# Sheet2.net
KiCad netlist of a schematic drawn in Altium Designer
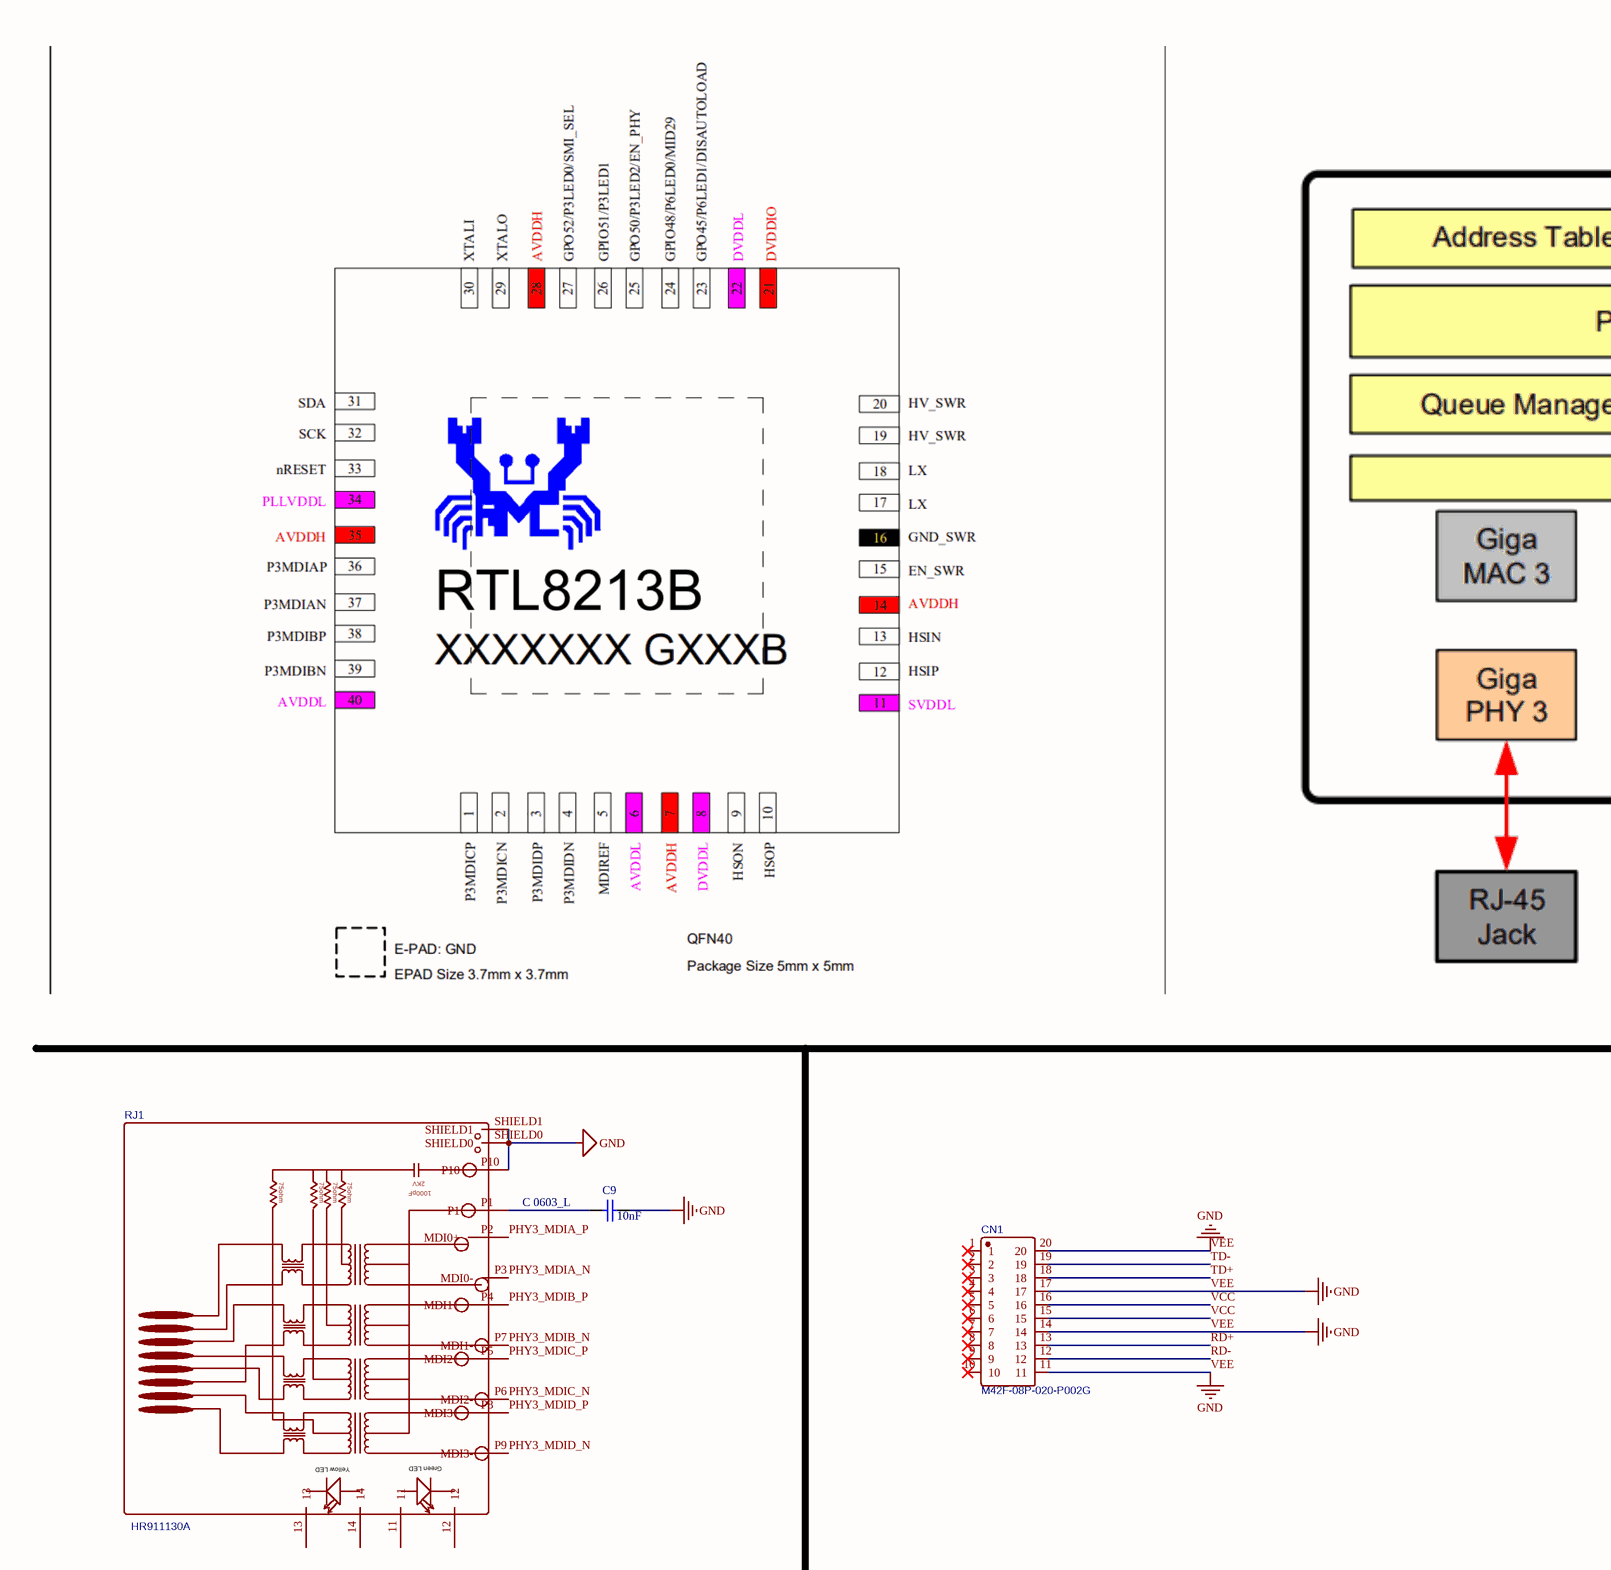
[diagram p0: Sheet2.SchDoc, top left]
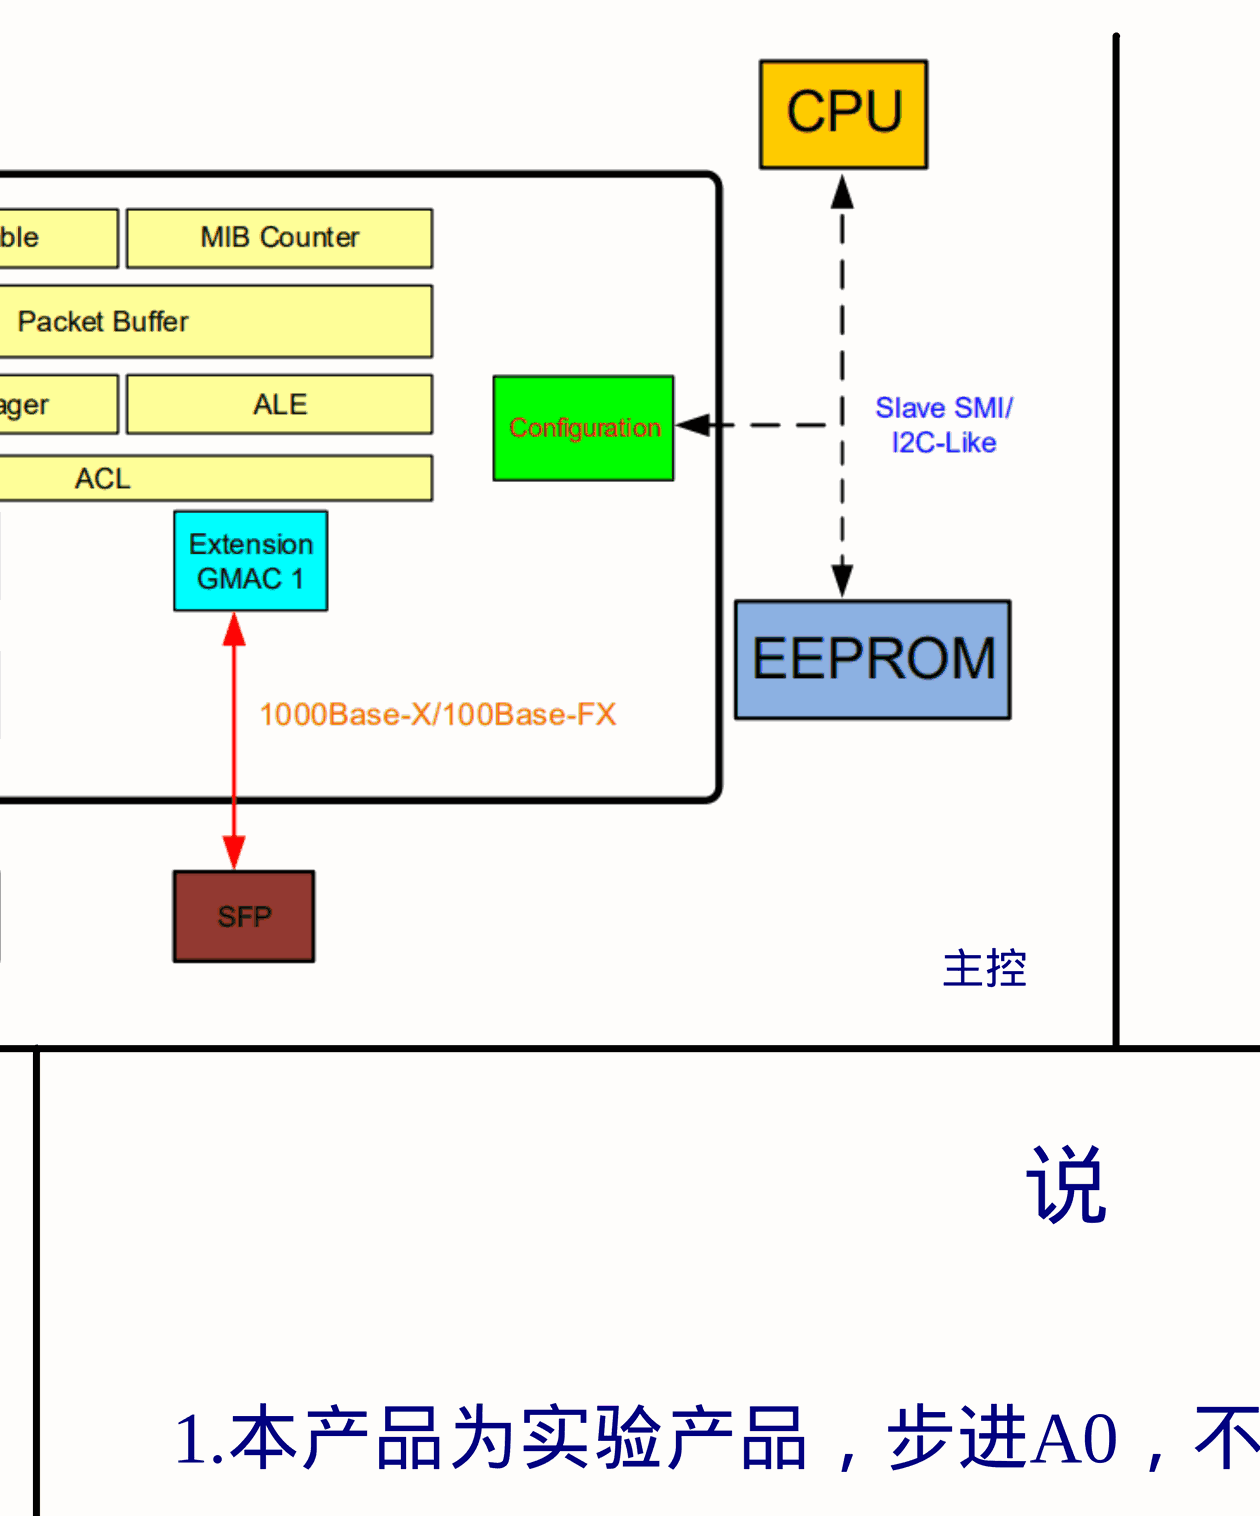
[diagram p1: Sheet2.SchDoc, top middle]
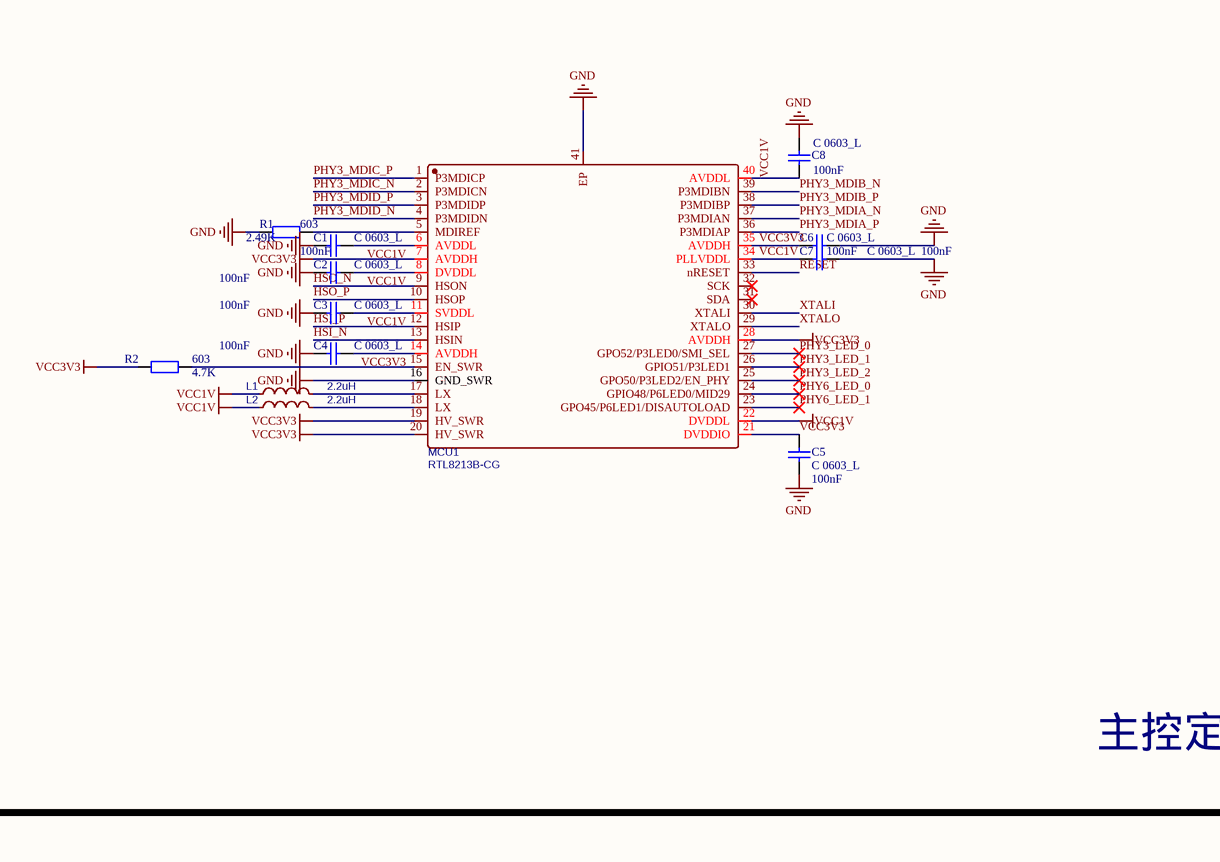
[diagram p2: Sheet2.SchDoc, top right]
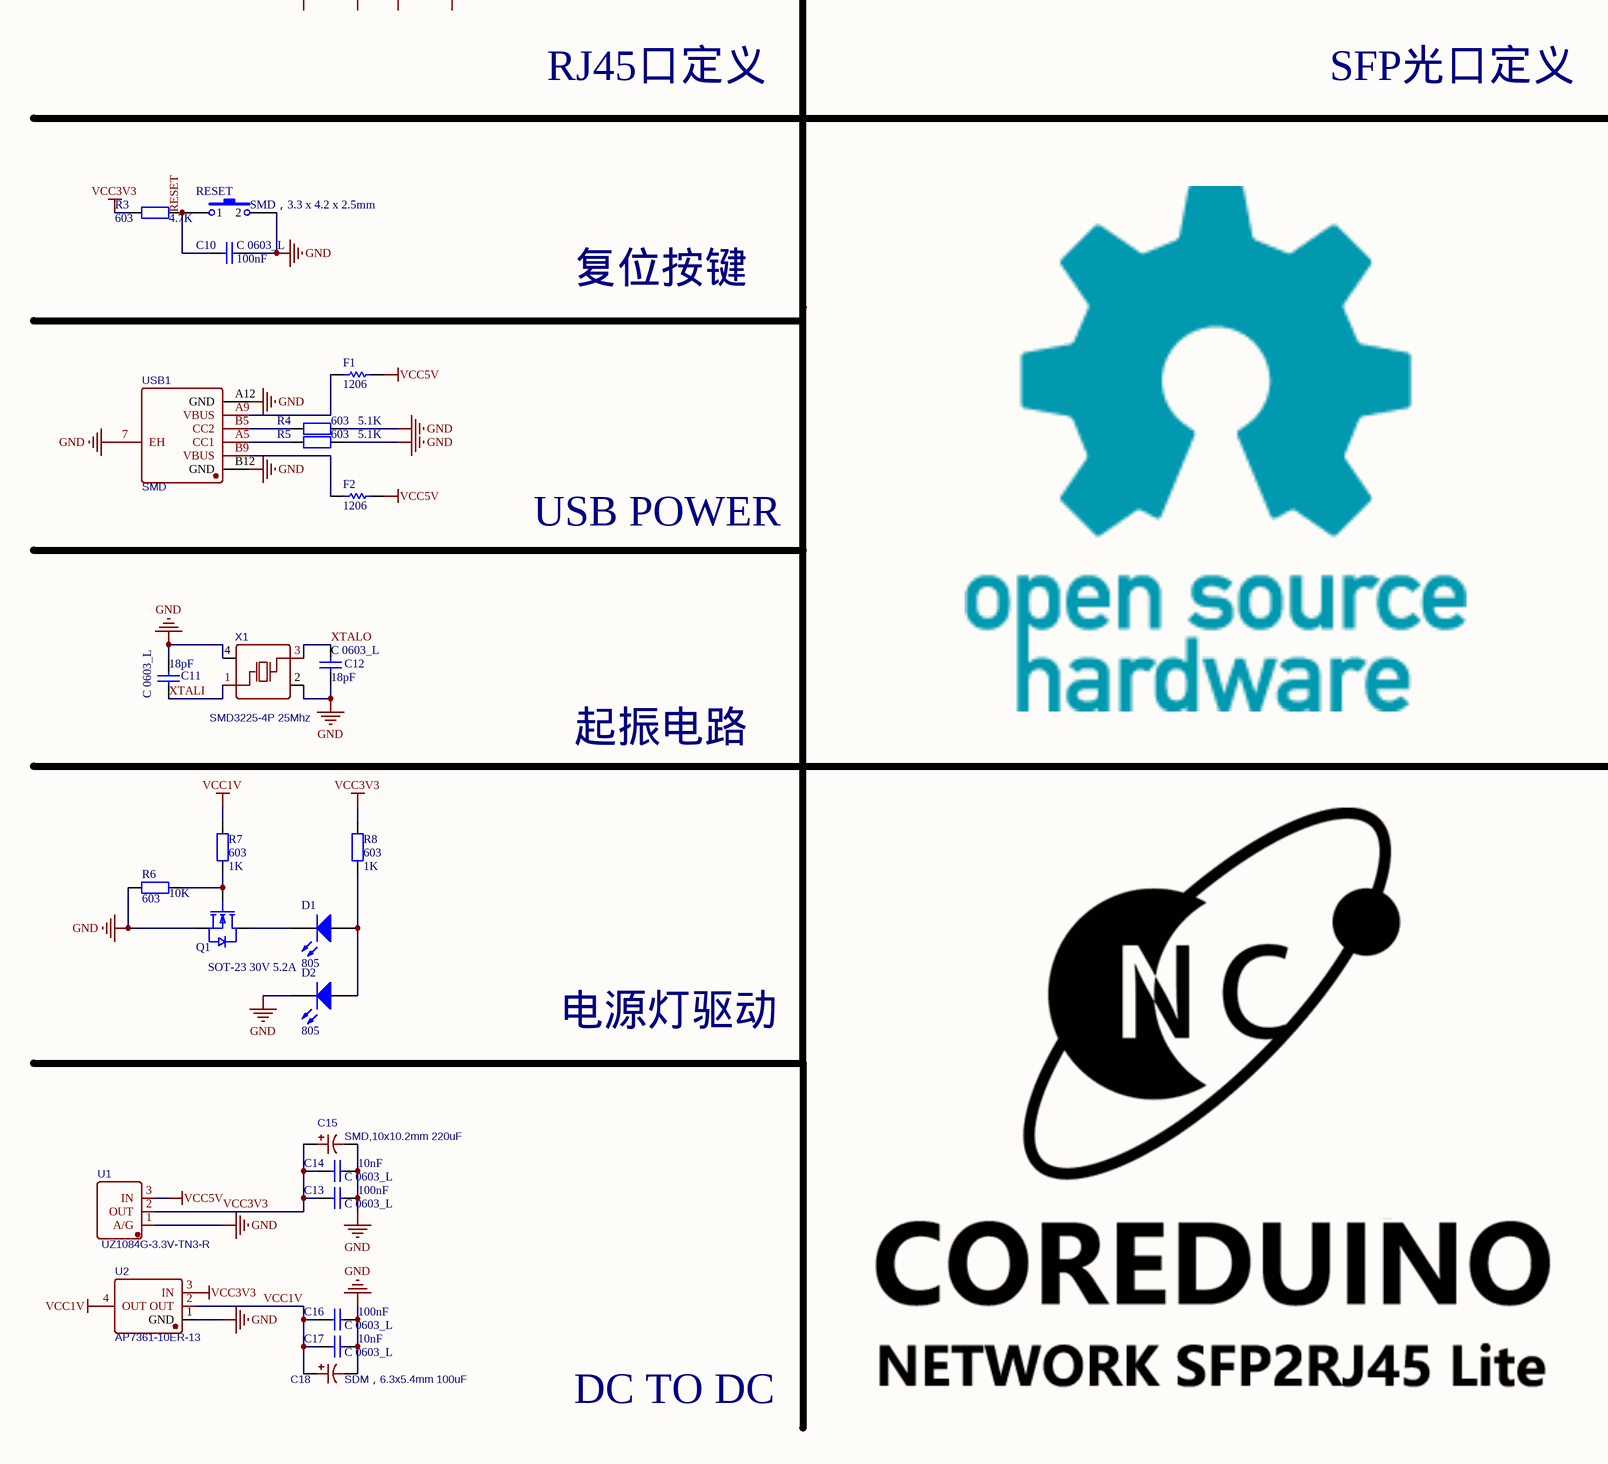
[diagram p3: Sheet2.SchDoc, bottom left]
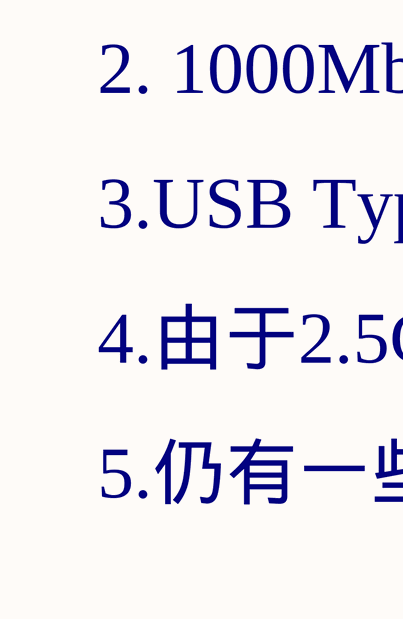
[diagram p4: Sheet2.SchDoc, bottom middle]

(export (version "E")
  (design (tool "Eeschema 10.0.6"))
  (components
    (comp (ref "C1")
      (value "C 0603_L")
      (footprint "C 0603_L")
      (description "贴片电容器（Capacitor）")
      (fields (field (name "ALTIUM_VALUE") "100nF") (field (name "PUBLISHER") "Altium Limited"))
      (libsource (lib "BaseLib") (part "C 0603_L"))
    )
    (comp (ref "C2")
      (value "C 0603_L")
      (footprint "C 0603_L")
      (description "贴片电容器（Capacitor）")
      (fields (field (name "ALTIUM_VALUE") "100nF") (field (name "PUBLISHER") "Altium Limited"))
      (libsource (lib "BaseLib") (part "C 0603_L"))
    )
    (comp (ref "C3")
      (value "C 0603_L")
      (footprint "C 0603_L")
      (description "贴片电容器（Capacitor）")
      (fields (field (name "ALTIUM_VALUE") "100nF") (field (name "PUBLISHER") "Altium Limited"))
      (libsource (lib "BaseLib") (part "C 0603_L"))
    )
    (comp (ref "C4")
      (value "C 0603_L")
      (footprint "C 0603_L")
      (description "贴片电容器（Capacitor）")
      (fields (field (name "ALTIUM_VALUE") "100nF") (field (name "PUBLISHER") "Altium Limited"))
      (libsource (lib "BaseLib") (part "C 0603_L"))
    )
    (comp (ref "C5")
      (value "C 0603_L")
      (footprint "C 0603_L")
      (description "贴片电容器（Capacitor）")
      (fields (field (name "ALTIUM_VALUE") "100nF") (field (name "PUBLISHER") "Altium Limited"))
      (libsource (lib "BaseLib") (part "C 0603_L"))
    )
    (comp (ref "C6")
      (value "C 0603_L")
      (footprint "C 0603_L")
      (description "贴片电容器（Capacitor）")
      (fields (field (name "ALTIUM_VALUE") "100nF") (field (name "PUBLISHER") "Altium Limited"))
      (libsource (lib "BaseLib") (part "C 0603_L"))
    )
    (comp (ref "C7")
      (value "C 0603_L")
      (footprint "C 0603_L")
      (description "贴片电容器（Capacitor）")
      (fields (field (name "ALTIUM_VALUE") "100nF") (field (name "PUBLISHER") "Altium Limited"))
      (libsource (lib "BaseLib") (part "C 0603_L"))
    )
    (comp (ref "C8")
      (value "C 0603_L")
      (footprint "C 0603_L")
      (description "贴片电容器（Capacitor）")
      (fields (field (name "ALTIUM_VALUE") "100nF") (field (name "PUBLISHER") "Altium Limited"))
      (libsource (lib "BaseLib") (part "C 0603_L"))
    )
    (comp (ref "C9")
      (value "C 0603_L")
      (footprint "C 0603_L")
      (description "贴片电容器（Capacitor）")
      (fields (field (name "ALTIUM_VALUE") "10nF") (field (name "PUBLISHER") "Altium Limited"))
      (libsource (lib "BaseLib") (part "C 0603_L"))
    )
    (comp (ref "C10")
      (value "C 0603_L")
      (footprint "C 0603_L")
      (description "贴片电容器（Capacitor）")
      (fields (field (name "ALTIUM_VALUE") "100nF") (field (name "PUBLISHER") "Altium Limited"))
      (libsource (lib "BaseLib") (part "C 0603_L"))
    )
    (comp (ref "C11")
      (value "C 0603_L")
      (footprint "C 0603_L")
      (description "贴片电容器（Capacitor）")
      (fields (field (name "ALTIUM_VALUE") "18pF") (field (name "PUBLISHER") "Altium Limited"))
      (libsource (lib "BaseLib") (part "C 0603_L"))
    )
    (comp (ref "C12")
      (value "C 0603_L")
      (footprint "C 0603_L")
      (description "贴片电容器（Capacitor）")
      (fields (field (name "ALTIUM_VALUE") "18pF") (field (name "PUBLISHER") "Altium Limited"))
      (libsource (lib "BaseLib") (part "C 0603_L"))
    )
    (comp (ref "C13")
      (value "C 0603_L")
      (footprint "C 0603_L")
      (description "贴片电容器（Capacitor）")
      (fields (field (name "ALTIUM_VALUE") "100nF") (field (name "PUBLISHER") "Altium Limited"))
      (libsource (lib "BaseLib") (part "C 0603_L"))
    )
    (comp (ref "C14")
      (value "C 0603_L")
      (footprint "C 0603_L")
      (description "贴片电容器（Capacitor）")
      (fields (field (name "ALTIUM_VALUE") "10nF") (field (name "PUBLISHER") "Altium Limited"))
      (libsource (lib "BaseLib") (part "C 0603_L"))
    )
    (comp (ref "C15")
      (value "SMD,10x10.2mm 220uF")
      (footprint "CAP-SMD_BD10.0-L10.3-W10.3-LS11.0-FD")
      (description "贴片铝电解电容器（Capacitor）")
      (fields
        (field (name "BOM_SUPPLIER PART") "C2887271")
        (field (name "BOM_MANUFACTURER PART") "RVT220UF50V67RV0021")
        (field (name "CONTRIBUTOR") "LCSC")
      )
      (libsource (lib "BaseLib") (part "RVT220UF50V67RV0021"))
    )
    (comp (ref "C16")
      (value "C 0603_L")
      (footprint "C 0603_L")
      (description "贴片电容器（Capacitor）")
      (fields (field (name "ALTIUM_VALUE") "100nF") (field (name "PUBLISHER") "Altium Limited"))
      (libsource (lib "BaseLib") (part "C 0603_L"))
    )
    (comp (ref "C17")
      (value "C 0603_L")
      (footprint "C 0603_L")
      (description "贴片电容器（Capacitor）")
      (fields (field (name "ALTIUM_VALUE") "10nF") (field (name "PUBLISHER") "Altium Limited"))
      (libsource (lib "BaseLib") (part "C 0603_L"))
    )
    (comp (ref "C18")
      (value "SDM，6.3x5.4mm 100uF")
      (footprint "CAP-SMD_BD6.3-L6.6-W6.6-LS7.2-FD")
      (description "贴片铝电解电容器（Capacitor）")
      (fields
        (field (name "BOM_SUPPLIER PART") "C2887276")
        (field (name "BOM_MANUFACTURER PART") "RVT100UF16V67RV0016")
        (field (name "CONTRIBUTOR") "LCSC")
      )
      (libsource (lib "BaseLib") (part "RVT100UF16V67RV0016"))
    )
    (comp (ref "CN1")
      (value "M42F-08P-020-P002G")
      (footprint "CONN-SMD_20P-P0.80-H_M42F-08P-020-P002G")
      (description "SFP+万兆光模块口（SFP+ Jack）")
      (fields (field (name "BOM_SUPPLIER PART") "C404107") (field (name "CONTRIBUTOR") "LCSC"))
      (libsource (lib "BaseLib") (part "M42F-08P-020-P002G"))
    )
    (comp (ref "D1")
      (value "805")
      (footprint "LED 0805G")
      (description "贴片发光二极管（LED）")
      (fields (field (name "PUBLISHER") "Altium Limited"))
      (libsource (lib "BaseLib") (part "LED 0805G 绿"))
    )
    (comp (ref "D2")
      (value "805")
      (footprint "LED 0805G")
      (description "贴片发光二极管（LED）")
      (fields (field (name "PUBLISHER") "Altium Limited"))
      (libsource (lib "BaseLib") (part "LED 0805G 绿"))
    )
    (comp (ref "F1")
      (value "1206")
      (footprint "FU 1206")
      (description "自恢复保险丝（Fuse）")
      (fields (field (name "PUBLISHER") "Altium Limited"))
      (libsource (lib "BaseLib") (part "nsmd150"))
    )
    (comp (ref "F2")
      (value "1206")
      (footprint "FU 1206")
      (description "自恢复保险丝（Fuse）")
      (fields (field (name "PUBLISHER") "Altium Limited"))
      (libsource (lib "BaseLib") (part "nsmd150"))
    )
    (comp (ref "L1")
      (value "2.2uH")
      (footprint "L0603")
      (description "贴片电感（Inductors）")
      (fields
        (field (name "BOM_MANUFACTURER PART") "SDFL1608Q2R2KTF")
        (field (name "BOM_SUPPLIER PART") "C1033")
      )
      (libsource (lib "BaseLib") (part "SDFL1608Q2R2KTF"))
    )
    (comp (ref "L2")
      (value "2.2uH")
      (footprint "L0603")
      (description "贴片电感（Inductors）")
      (fields
        (field (name "BOM_MANUFACTURER PART") "SDFL1608Q2R2KTF")
        (field (name "BOM_SUPPLIER PART") "C1033")
      )
      (libsource (lib "BaseLib") (part "SDFL1608Q2R2KTF"))
    )
    (comp (ref "MCU1")
      (value "RTL8213B-CG")
      (footprint "QFN-40_L5.0-W5.0-P0.40-BL-EP3.7")
      (description "以太网转换芯片（Network）")
      (fields (field (name "BOM_SUPPLIER PART") "C2766076") (field (name "CONTRIBUTOR") "LCSC"))
      (libsource (lib "BaseLib") (part "RTL8213B-CG"))
    )
    (comp (ref "Q1")
      (value "SOT-23 30V 5.2A")
      (footprint "AO3400A")
      (description "场效应管（MOSFET）")
      (fields (field (name "MANUFACTURER") "Nexperia(安世)") (field (name "MANUFACTURER PART") "2N7002,215"))
      (libsource (lib "BaseLib") (part "AO3400A"))
    )
    (comp (ref "R1")
      (value "603")
      (footprint "R 0603_L")
      (description "贴片电阻（Resistor）")
      (fields (field (name "ALTIUM_VALUE") "2.49K") (field (name "PUBLISHER") "Altium Limited"))
      (libsource (lib "BaseLib") (part "R 0603_L"))
    )
    (comp (ref "R2")
      (value "603")
      (footprint "R 0603_L")
      (description "贴片电阻（Resistor）")
      (fields (field (name "ALTIUM_VALUE") "4.7K") (field (name "PUBLISHER") "Altium Limited"))
      (libsource (lib "BaseLib") (part "R 0603_L"))
    )
    (comp (ref "R3")
      (value "603")
      (footprint "R 0603_L")
      (description "贴片电阻（Resistor）")
      (fields (field (name "ALTIUM_VALUE") "4.7K") (field (name "PUBLISHER") "Altium Limited"))
      (libsource (lib "BaseLib") (part "R 0603_L"))
    )
    (comp (ref "R4")
      (value "603")
      (footprint "R 0603_L")
      (description "贴片电阻（Resistor）")
      (fields (field (name "ALTIUM_VALUE") "5.1K") (field (name "PUBLISHER") "Altium Limited"))
      (libsource (lib "BaseLib") (part "R 0603_L"))
    )
    (comp (ref "R5")
      (value "603")
      (footprint "R 0603_L")
      (description "贴片电阻（Resistor）")
      (fields (field (name "ALTIUM_VALUE") "5.1K") (field (name "PUBLISHER") "Altium Limited"))
      (libsource (lib "BaseLib") (part "R 0603_L"))
    )
    (comp (ref "R6")
      (value "603")
      (footprint "R 0603_L")
      (description "贴片电阻（Resistor）")
      (fields (field (name "ALTIUM_VALUE") "10K") (field (name "PUBLISHER") "Altium Limited"))
      (libsource (lib "BaseLib") (part "R 0603_L"))
    )
    (comp (ref "R7")
      (value "603")
      (footprint "R 0603_L")
      (description "贴片电阻（Resistor）")
      (fields (field (name "ALTIUM_VALUE") "1K") (field (name "PUBLISHER") "Altium Limited"))
      (libsource (lib "") (part "R 0603_L_1"))
    )
    (comp (ref "R8")
      (value "603")
      (footprint "R 0603_L")
      (description "贴片电阻（Resistor）")
      (fields (field (name "ALTIUM_VALUE") "1K") (field (name "PUBLISHER") "Altium Limited"))
      (libsource (lib "") (part "R 0603_L_1"))
    )
    (comp (ref "RESET")
      (value "SMD，3.3 x 4.2 x 2.5mm")
      (footprint "SMD-3.2*4.2")
      (description "轻触开关（Touch Switch）")
      (fields (field (name "PUBLISHER") "Altium Limited"))
      (libsource (lib "BaseLib") (part "260GF"))
    )
    (comp (ref "RJ1")
      (value "HR911130A")
      (footprint "RJ45-TH_HR911130A")
      (description "单插带灯以太网接口（RJ45）")
      (fields (field (name "BOM_SUPPLIER PART") "C54408"))
      (libsource (lib "BaseLib") (part "HR911130A"))
    )
    (comp (ref "U1")
      (value "UZ1084G-3.3V-TN3-R")
      (footprint "TO-252-3_L6.5-W5.8-P4.58-TL")
      (description "线性稳压器（LDO）")
      (fields (field (name "BOM_SUPPLIER PART") "C84897"))
      (libsource (lib "BaseLib") (part "UZ1084G-3.3V-TN3-R"))
    )
    (comp (ref "U2")
      (value "AP7361-10ER-13")
      (footprint "SOT-223_L6.5-W3.5-P2.30-LS7.0-BR")
      (description "线性稳压器（LDO）")
      (fields (field (name "BOM_SUPPLIER PART") "C460389") (field (name "CONTRIBUTOR") "LCSC"))
      (libsource (lib "BaseLib") (part "AP7361-10ER-13"))
    )
    (comp (ref "USB1")
      (value "SMD")
      (footprint "TYPE-C-SMD_TYPE-C-6P")
      (description "通用通信总线接口（USB）")
      (fields
        (field (name "BOM_SUPPLIER PART") "C456012")
        (field (name "BOM_MANUFACTURER PART") "TYPE-C 6P")
        (field (name "CONTRIBUTOR") "LCSC")
      )
      (libsource (lib "BaseLib") (part "TYPE-C 6P QT"))
    )
    (comp (ref "X1")
      (value "SMD3225-4P 25Mhz")
      (footprint "OSC-SMD_4P-L3.2-W2.5-BL")
      (description "无源晶振（Crystal）")
      (fields
        (field (name "BOM_SUPPLIER PART") "C117869")
        (field (name "BOM_MANUFACTURER PART") "XXCEELNANF-25MHZ")
        (field (name "CONTRIBUTOR") "LCSC")
      )
      (libsource (lib "BaseLib") (part "XXCEELNANF-25MHZ"))
    )
  )
  (nets
    (net (code "1") (name "/HSI_N") (class "Default")
      (node (ref "MCU1") (pin "13") (pinfunction "HSIN_13") (pintype "passive"))
    )
    (net (code "2") (name "/HSI_P") (class "Default")
      (node (ref "MCU1") (pin "12") (pinfunction "HSIP_12") (pintype "passive"))
    )
    (net (code "3") (name "/HSO_N") (class "Default")
      (node (ref "MCU1") (pin "9") (pinfunction "HSON_9") (pintype "passive"))
    )
    (net (code "4") (name "/HSO_P") (class "Default")
      (node (ref "MCU1") (pin "10") (pinfunction "HSOP_10") (pintype "passive"))
    )
    (net (code "5") (name "/PHY3_LED_0") (class "Default")
      (node (ref "MCU1") (pin "27") (pinfunction "GPO52/P3LED0/SMI_SEL_27") (pintype "passive+no_connect"))
    )
    (net (code "6") (name "/PHY3_LED_1") (class "Default")
      (node (ref "MCU1") (pin "26") (pinfunction "GPIO51/P3LED1_26") (pintype "passive+no_connect"))
    )
    (net (code "7") (name "/PHY3_LED_2") (class "Default")
      (node (ref "MCU1") (pin "25") (pinfunction "GPO50/P3LED2/EN_PHY_25") (pintype "passive+no_connect"))
    )
    (net (code "8") (name "/PHY3_MDIA_N") (class "Default")
      (node (ref "MCU1") (pin "37") (pinfunction "P3MDIAN_37") (pintype "passive"))
      (node (ref "RJ1") (pin "P3") (pinfunction "MDI0-_P3") (pintype "passive"))
    )
    (net (code "9") (name "/PHY3_MDIA_P") (class "Default")
      (node (ref "MCU1") (pin "36") (pinfunction "P3MDIAP_36") (pintype "passive"))
      (node (ref "RJ1") (pin "P2") (pinfunction "MDI0+_P2") (pintype "passive"))
    )
    (net (code "10") (name "/PHY3_MDIB_N") (class "Default")
      (node (ref "MCU1") (pin "39") (pinfunction "P3MDIBN_39") (pintype "passive"))
      (node (ref "RJ1") (pin "P7") (pinfunction "MDI1-_P7") (pintype "passive"))
    )
    (net (code "11") (name "/PHY3_MDIB_P") (class "Default")
      (node (ref "MCU1") (pin "38") (pinfunction "P3MDIBP_38") (pintype "passive"))
      (node (ref "RJ1") (pin "P4") (pinfunction "MDI1+_P4") (pintype "passive"))
    )
    (net (code "12") (name "/PHY3_MDIC_N") (class "Default")
      (node (ref "MCU1") (pin "2") (pinfunction "P3MDICN_2") (pintype "passive"))
      (node (ref "RJ1") (pin "P6") (pinfunction "MDI2-_P6") (pintype "passive"))
    )
    (net (code "13") (name "/PHY3_MDIC_P") (class "Default")
      (node (ref "MCU1") (pin "1") (pinfunction "P3MDICP_1") (pintype "passive"))
      (node (ref "RJ1") (pin "P5") (pinfunction "MDI2+_P5") (pintype "passive"))
    )
    (net (code "14") (name "/PHY3_MDID_N") (class "Default")
      (node (ref "MCU1") (pin "4") (pinfunction "P3MDIDN_4") (pintype "passive"))
      (node (ref "RJ1") (pin "P9") (pinfunction "MDI3-_P9") (pintype "passive"))
    )
    (net (code "15") (name "/PHY3_MDID_P") (class "Default")
      (node (ref "MCU1") (pin "3") (pinfunction "P3MDIDP_3") (pintype "passive"))
      (node (ref "RJ1") (pin "P8") (pinfunction "MDI3+_P8") (pintype "passive"))
    )
    (net (code "16") (name "/PHY6_LED_0") (class "Default")
      (node (ref "MCU1") (pin "24") (pinfunction "GPIO48/P6LED0/MID29_24") (pintype "passive+no_connect"))
    )
    (net (code "17") (name "/PHY6_LED_1") (class "Default")
      (node (ref "MCU1") (pin "23") (pinfunction "GPO45/P6LED1/DISAUTOLOAD_23") (pintype "passive+no_connect"))
    )
    (net (code "18") (name "/RD+") (class "Default")
      (node (ref "CN1") (pin "13") (pinfunction "13_13") (pintype "passive"))
    )
    (net (code "19") (name "/RD-") (class "Default")
      (node (ref "CN1") (pin "12") (pinfunction "12_12") (pintype "passive"))
    )
    (net (code "20") (name "/RESET") (class "Default")
      (node (ref "C10") (pin "1") (pinfunction "1_1") (pintype "passive"))
      (node (ref "MCU1") (pin "33") (pinfunction "nRESET_33") (pintype "passive"))
      (node (ref "R3") (pin "2") (pinfunction "2_2") (pintype "passive"))
      (node (ref "RESET") (pin "1") (pinfunction "1_1") (pintype "passive"))
    )
    (net (code "21") (name "/TD+") (class "Default")
      (node (ref "CN1") (pin "18") (pinfunction "18_18") (pintype "passive"))
    )
    (net (code "22") (name "/TD-") (class "Default")
      (node (ref "CN1") (pin "19") (pinfunction "19_19") (pintype "passive"))
    )
    (net (code "23") (name "/VCC") (class "Default")
      (node (ref "CN1") (pin "15") (pinfunction "15_15") (pintype "passive"))
      (node (ref "CN1") (pin "16") (pinfunction "16_16") (pintype "passive"))
    )
    (net (code "24") (name "/XTALI") (class "Default")
      (node (ref "C11") (pin "1") (pinfunction "1_1") (pintype "passive"))
      (node (ref "MCU1") (pin "30") (pinfunction "XTALI_30") (pintype "passive"))
      (node (ref "X1") (pin "1") (pinfunction "OSC1_1") (pintype "passive"))
    )
    (net (code "25") (name "/XTALO") (class "Default")
      (node (ref "C12") (pin "2") (pinfunction "2_2") (pintype "passive"))
      (node (ref "MCU1") (pin "29") (pinfunction "XTALO_29") (pintype "passive"))
      (node (ref "X1") (pin "3") (pinfunction "OSC2_3") (pintype "passive"))
    )
    (net (code "26") (name "GND") (class "Default")
      (node (ref "C1") (pin "1") (pinfunction "1_1") (pintype "passive"))
      (node (ref "C10") (pin "2") (pinfunction "2_2") (pintype "passive"))
      (node (ref "C11") (pin "2") (pinfunction "2_2") (pintype "passive"))
      (node (ref "C12") (pin "1") (pinfunction "1_1") (pintype "passive"))
      (node (ref "C13") (pin "2") (pinfunction "2_2") (pintype "passive"))
      (node (ref "C14") (pin "2") (pinfunction "2_2") (pintype "passive"))
      (node (ref "C15") (pin "2") (pinfunction "2_2") (pintype "passive"))
      (node (ref "C16") (pin "2") (pinfunction "2_2") (pintype "passive"))
      (node (ref "C17") (pin "2") (pinfunction "2_2") (pintype "passive"))
      (node (ref "C18") (pin "2") (pinfunction "2_2") (pintype "passive"))
      (node (ref "C2") (pin "1") (pinfunction "1_1") (pintype "passive"))
      (node (ref "C3") (pin "1") (pinfunction "1_1") (pintype "passive"))
      (node (ref "C4") (pin "1") (pinfunction "1_1") (pintype "passive"))
      (node (ref "C5") (pin "2") (pinfunction "2_2") (pintype "passive"))
      (node (ref "C6") (pin "2") (pinfunction "2_2") (pintype "passive"))
      (node (ref "C7") (pin "2") (pinfunction "2_2") (pintype "passive"))
      (node (ref "C8") (pin "2") (pinfunction "2_2") (pintype "passive"))
      (node (ref "C9") (pin "2") (pinfunction "2_2") (pintype "passive"))
      (node (ref "CN1") (pin "11") (pinfunction "11_11") (pintype "passive"))
      (node (ref "CN1") (pin "14") (pinfunction "14_14") (pintype "passive"))
      (node (ref "CN1") (pin "17") (pinfunction "17_17") (pintype "passive"))
      (node (ref "CN1") (pin "20") (pinfunction "20_20") (pintype "passive"))
      (node (ref "D2") (pin "2") (pinfunction "K_2") (pintype "passive"))
      (node (ref "MCU1") (pin "16") (pinfunction "GND_SWR_16") (pintype "passive"))
      (node (ref "MCU1") (pin "41") (pinfunction "EP_41") (pintype "passive"))
      (node (ref "Q1") (pin "2") (pinfunction "S_2") (pintype "passive"))
      (node (ref "R1") (pin "1") (pinfunction "1_1") (pintype "passive"))
      (node (ref "R4") (pin "2") (pinfunction "2_2") (pintype "passive"))
      (node (ref "R5") (pin "2") (pinfunction "2_2") (pintype "passive"))
      (node (ref "R6") (pin "1") (pinfunction "1_1") (pintype "passive"))
      (node (ref "RESET") (pin "2") (pinfunction "2_2") (pintype "passive"))
      (node (ref "RJ1") (pin "P10") (pinfunction "P10_P10") (pintype "passive"))
      (node (ref "RJ1") (pin "SHIELD0") (pinfunction "SHIELD0_SHIELD0") (pintype "passive"))
      (node (ref "RJ1") (pin "SHIELD1") (pinfunction "SHIELD1_SHIELD1") (pintype "passive"))
      (node (ref "U1") (pin "1") (pinfunction "A/G_1") (pintype "passive"))
      (node (ref "U2") (pin "1") (pinfunction "GND_1") (pintype "passive"))
      (node (ref "USB1") (pin "7") (pinfunction "EH_7") (pintype "passive"))
      (node (ref "USB1") (pin "A12") (pinfunction "GND_A12") (pintype "passive"))
      (node (ref "USB1") (pin "B12") (pinfunction "GND_B12") (pintype "passive"))
      (node (ref "X1") (pin "2") (pinfunction "GND_2") (pintype "passive"))
      (node (ref "X1") (pin "4") (pinfunction "GND_4") (pintype "passive"))
    )
    (net (code "27") (name "Net-(C9-Pad1)") (class "Default")
      (node (ref "C9") (pin "1") (pinfunction "1_1") (pintype "passive"))
      (node (ref "RJ1") (pin "P1") (pinfunction "P1_P1") (pintype "passive"))
    )
    (net (code "28") (name "Net-(D1-A)") (class "Default")
      (node (ref "D1") (pin "1") (pinfunction "A_1") (pintype "passive"))
      (node (ref "D2") (pin "1") (pinfunction "A_1") (pintype "passive"))
      (node (ref "R8") (pin "1") (pinfunction "1_1") (pintype "passive"))
    )
    (net (code "29") (name "Net-(D1-K)") (class "Default")
      (node (ref "D1") (pin "2") (pinfunction "K_2") (pintype "passive"))
      (node (ref "Q1") (pin "3") (pinfunction "D_3") (pintype "passive"))
    )
    (net (code "30") (name "Net-(F1-Pad1)") (class "Default")
      (node (ref "F1") (pin "1") (pinfunction "1_1") (pintype "passive"))
      (node (ref "USB1") (pin "A9") (pinfunction "VBUS_A9") (pintype "passive"))
    )
    (net (code "31") (name "Net-(F2-Pad1)") (class "Default")
      (node (ref "F2") (pin "1") (pinfunction "1_1") (pintype "passive"))
      (node (ref "USB1") (pin "B9") (pinfunction "VBUS_B9") (pintype "passive"))
    )
    (net (code "32") (name "Net-(L1-Pad2)") (class "Default")
      (node (ref "L1") (pin "2") (pinfunction "2_2") (pintype "passive"))
      (node (ref "MCU1") (pin "17") (pinfunction "LX_17") (pintype "passive"))
    )
    (net (code "33") (name "Net-(L2-Pad2)") (class "Default")
      (node (ref "L2") (pin "2") (pinfunction "2_2") (pintype "passive"))
      (node (ref "MCU1") (pin "18") (pinfunction "LX_18") (pintype "passive"))
    )
    (net (code "34") (name "Net-(MCU1-EN_SWR)") (class "Default")
      (node (ref "MCU1") (pin "15") (pinfunction "EN_SWR_15") (pintype "passive"))
      (node (ref "R2") (pin "2") (pinfunction "2_2") (pintype "passive"))
    )
    (net (code "35") (name "Net-(MCU1-MDIREF)") (class "Default")
      (node (ref "MCU1") (pin "5") (pinfunction "MDIREF_5") (pintype "passive"))
      (node (ref "R1") (pin "2") (pinfunction "2_2") (pintype "passive"))
    )
    (net (code "36") (name "Net-(Q1-G)") (class "Default")
      (node (ref "Q1") (pin "1") (pinfunction "G_1") (pintype "passive"))
      (node (ref "R6") (pin "2") (pinfunction "2_2") (pintype "passive"))
      (node (ref "R7") (pin "1") (pinfunction "1_1") (pintype "passive"))
    )
    (net (code "37") (name "Net-(USB1-CC1)") (class "Default")
      (node (ref "R5") (pin "1") (pinfunction "1_1") (pintype "passive"))
      (node (ref "USB1") (pin "A5") (pinfunction "CC1_A5") (pintype "passive"))
    )
    (net (code "38") (name "Net-(USB1-CC2)") (class "Default")
      (node (ref "R4") (pin "1") (pinfunction "1_1") (pintype "passive"))
      (node (ref "USB1") (pin "B5") (pinfunction "CC2_B5") (pintype "passive"))
    )
    (net (code "39") (name "VCC1V") (class "Default")
      (node (ref "C1") (pin "2") (pinfunction "2_2") (pintype "passive"))
      (node (ref "C16") (pin "1") (pinfunction "1_1") (pintype "passive"))
      (node (ref "C17") (pin "1") (pinfunction "1_1") (pintype "passive"))
      (node (ref "C18") (pin "1") (pinfunction "1_1") (pintype "passive"))
      (node (ref "C2") (pin "2") (pinfunction "2_2") (pintype "passive"))
      (node (ref "C3") (pin "2") (pinfunction "2_2") (pintype "passive"))
      (node (ref "C7") (pin "1") (pinfunction "1_1") (pintype "passive"))
      (node (ref "C8") (pin "1") (pinfunction "1_1") (pintype "passive"))
      (node (ref "L1") (pin "1") (pinfunction "1_1") (pintype "passive"))
      (node (ref "L2") (pin "1") (pinfunction "1_1") (pintype "passive"))
      (node (ref "MCU1") (pin "11") (pinfunction "SVDDL_11") (pintype "passive"))
      (node (ref "MCU1") (pin "22") (pinfunction "DVDDL_22") (pintype "passive"))
      (node (ref "MCU1") (pin "34") (pinfunction "PLLVDDL_34") (pintype "passive"))
      (node (ref "MCU1") (pin "40") (pinfunction "AVDDL_40") (pintype "passive"))
      (node (ref "MCU1") (pin "6") (pinfunction "AVDDL_6") (pintype "passive"))
      (node (ref "MCU1") (pin "8") (pinfunction "DVDDL_8") (pintype "passive"))
      (node (ref "R7") (pin "2") (pinfunction "2_2") (pintype "passive"))
      (node (ref "U2") (pin "2") (pinfunction "OUT_2") (pintype "passive"))
      (node (ref "U2") (pin "4") (pinfunction "OUT_4") (pintype "passive"))
    )
    (net (code "40") (name "VCC3V3") (class "Default")
      (node (ref "C13") (pin "1") (pinfunction "1_1") (pintype "passive"))
      (node (ref "C14") (pin "1") (pinfunction "1_1") (pintype "passive"))
      (node (ref "C15") (pin "1") (pinfunction "1_1") (pintype "passive"))
      (node (ref "C4") (pin "2") (pinfunction "2_2") (pintype "passive"))
      (node (ref "C5") (pin "1") (pinfunction "1_1") (pintype "passive"))
      (node (ref "C6") (pin "1") (pinfunction "1_1") (pintype "passive"))
      (node (ref "MCU1") (pin "14") (pinfunction "AVDDH_14") (pintype "passive"))
      (node (ref "MCU1") (pin "19") (pinfunction "HV_SWR_19") (pintype "passive"))
      (node (ref "MCU1") (pin "20") (pinfunction "HV_SWR_20") (pintype "passive"))
      (node (ref "MCU1") (pin "21") (pinfunction "DVDDIO_21") (pintype "passive"))
      (node (ref "MCU1") (pin "28") (pinfunction "AVDDH_28") (pintype "passive"))
      (node (ref "MCU1") (pin "35") (pinfunction "AVDDH_35") (pintype "passive"))
      (node (ref "MCU1") (pin "7") (pinfunction "AVDDH_7") (pintype "passive"))
      (node (ref "R2") (pin "1") (pinfunction "1_1") (pintype "passive"))
      (node (ref "R3") (pin "1") (pinfunction "1_1") (pintype "passive"))
      (node (ref "R8") (pin "2") (pinfunction "2_2") (pintype "passive"))
      (node (ref "U1") (pin "2") (pinfunction "OUT_2") (pintype "passive"))
      (node (ref "U2") (pin "3") (pinfunction "IN_3") (pintype "passive"))
    )
    (net (code "41") (name "VCC5V") (class "Default")
      (node (ref "F1") (pin "2") (pinfunction "2_2") (pintype "passive"))
      (node (ref "F2") (pin "2") (pinfunction "2_2") (pintype "passive"))
      (node (ref "U1") (pin "3") (pinfunction "IN_3") (pintype "passive"))
    )
    (net (code "42") (name "unconnected-(CN1-Pad1)") (class "Default")
      (node (ref "CN1") (pin "1") (pinfunction "1_1") (pintype "passive+no_connect"))
    )
    (net (code "43") (name "unconnected-(CN1-Pad2)") (class "Default")
      (node (ref "CN1") (pin "2") (pinfunction "2_2") (pintype "passive+no_connect"))
    )
    (net (code "44") (name "unconnected-(CN1-Pad3)") (class "Default")
      (node (ref "CN1") (pin "3") (pinfunction "3_3") (pintype "passive+no_connect"))
    )
    (net (code "45") (name "unconnected-(CN1-Pad4)") (class "Default")
      (node (ref "CN1") (pin "4") (pinfunction "4_4") (pintype "passive+no_connect"))
    )
    (net (code "46") (name "unconnected-(CN1-Pad5)") (class "Default")
      (node (ref "CN1") (pin "5") (pinfunction "5_5") (pintype "passive+no_connect"))
    )
    (net (code "47") (name "unconnected-(CN1-Pad6)") (class "Default")
      (node (ref "CN1") (pin "6") (pinfunction "6_6") (pintype "passive+no_connect"))
    )
    (net (code "48") (name "unconnected-(CN1-Pad7)") (class "Default")
      (node (ref "CN1") (pin "7") (pinfunction "7_7") (pintype "passive+no_connect"))
    )
    (net (code "49") (name "unconnected-(CN1-Pad8)") (class "Default")
      (node (ref "CN1") (pin "8") (pinfunction "8_8") (pintype "passive+no_connect"))
    )
    (net (code "50") (name "unconnected-(CN1-Pad9)") (class "Default")
      (node (ref "CN1") (pin "9") (pinfunction "9_9") (pintype "passive+no_connect"))
    )
    (net (code "51") (name "unconnected-(CN1-Pad10)") (class "Default")
      (node (ref "CN1") (pin "10") (pinfunction "10_10") (pintype "passive+no_connect"))
    )
    (net (code "52") (name "unconnected-(MCU1-SCK-Pad32)") (class "Default")
      (node (ref "MCU1") (pin "32") (pinfunction "SCK_32") (pintype "passive+no_connect"))
    )
    (net (code "53") (name "unconnected-(MCU1-SDA-Pad31)") (class "Default")
      (node (ref "MCU1") (pin "31") (pinfunction "SDA_31") (pintype "passive+no_connect"))
    )
    (net (code "54") (name "unconnected-(RJ1-Pad11)") (class "Default")
      (node (ref "RJ1") (pin "11") (pinfunction "11_11") (pintype "passive"))
    )
    (net (code "55") (name "unconnected-(RJ1-Pad12)") (class "Default")
      (node (ref "RJ1") (pin "12") (pinfunction "12_12") (pintype "passive"))
    )
    (net (code "56") (name "unconnected-(RJ1-Pad13)") (class "Default")
      (node (ref "RJ1") (pin "13") (pinfunction "13_13") (pintype "passive"))
    )
    (net (code "57") (name "unconnected-(RJ1-Pad14)") (class "Default")
      (node (ref "RJ1") (pin "14") (pinfunction "14_14") (pintype "passive"))
    )
  )
)
